# rev2.net
KiCad netlist of a schematic drawn in EAGLE
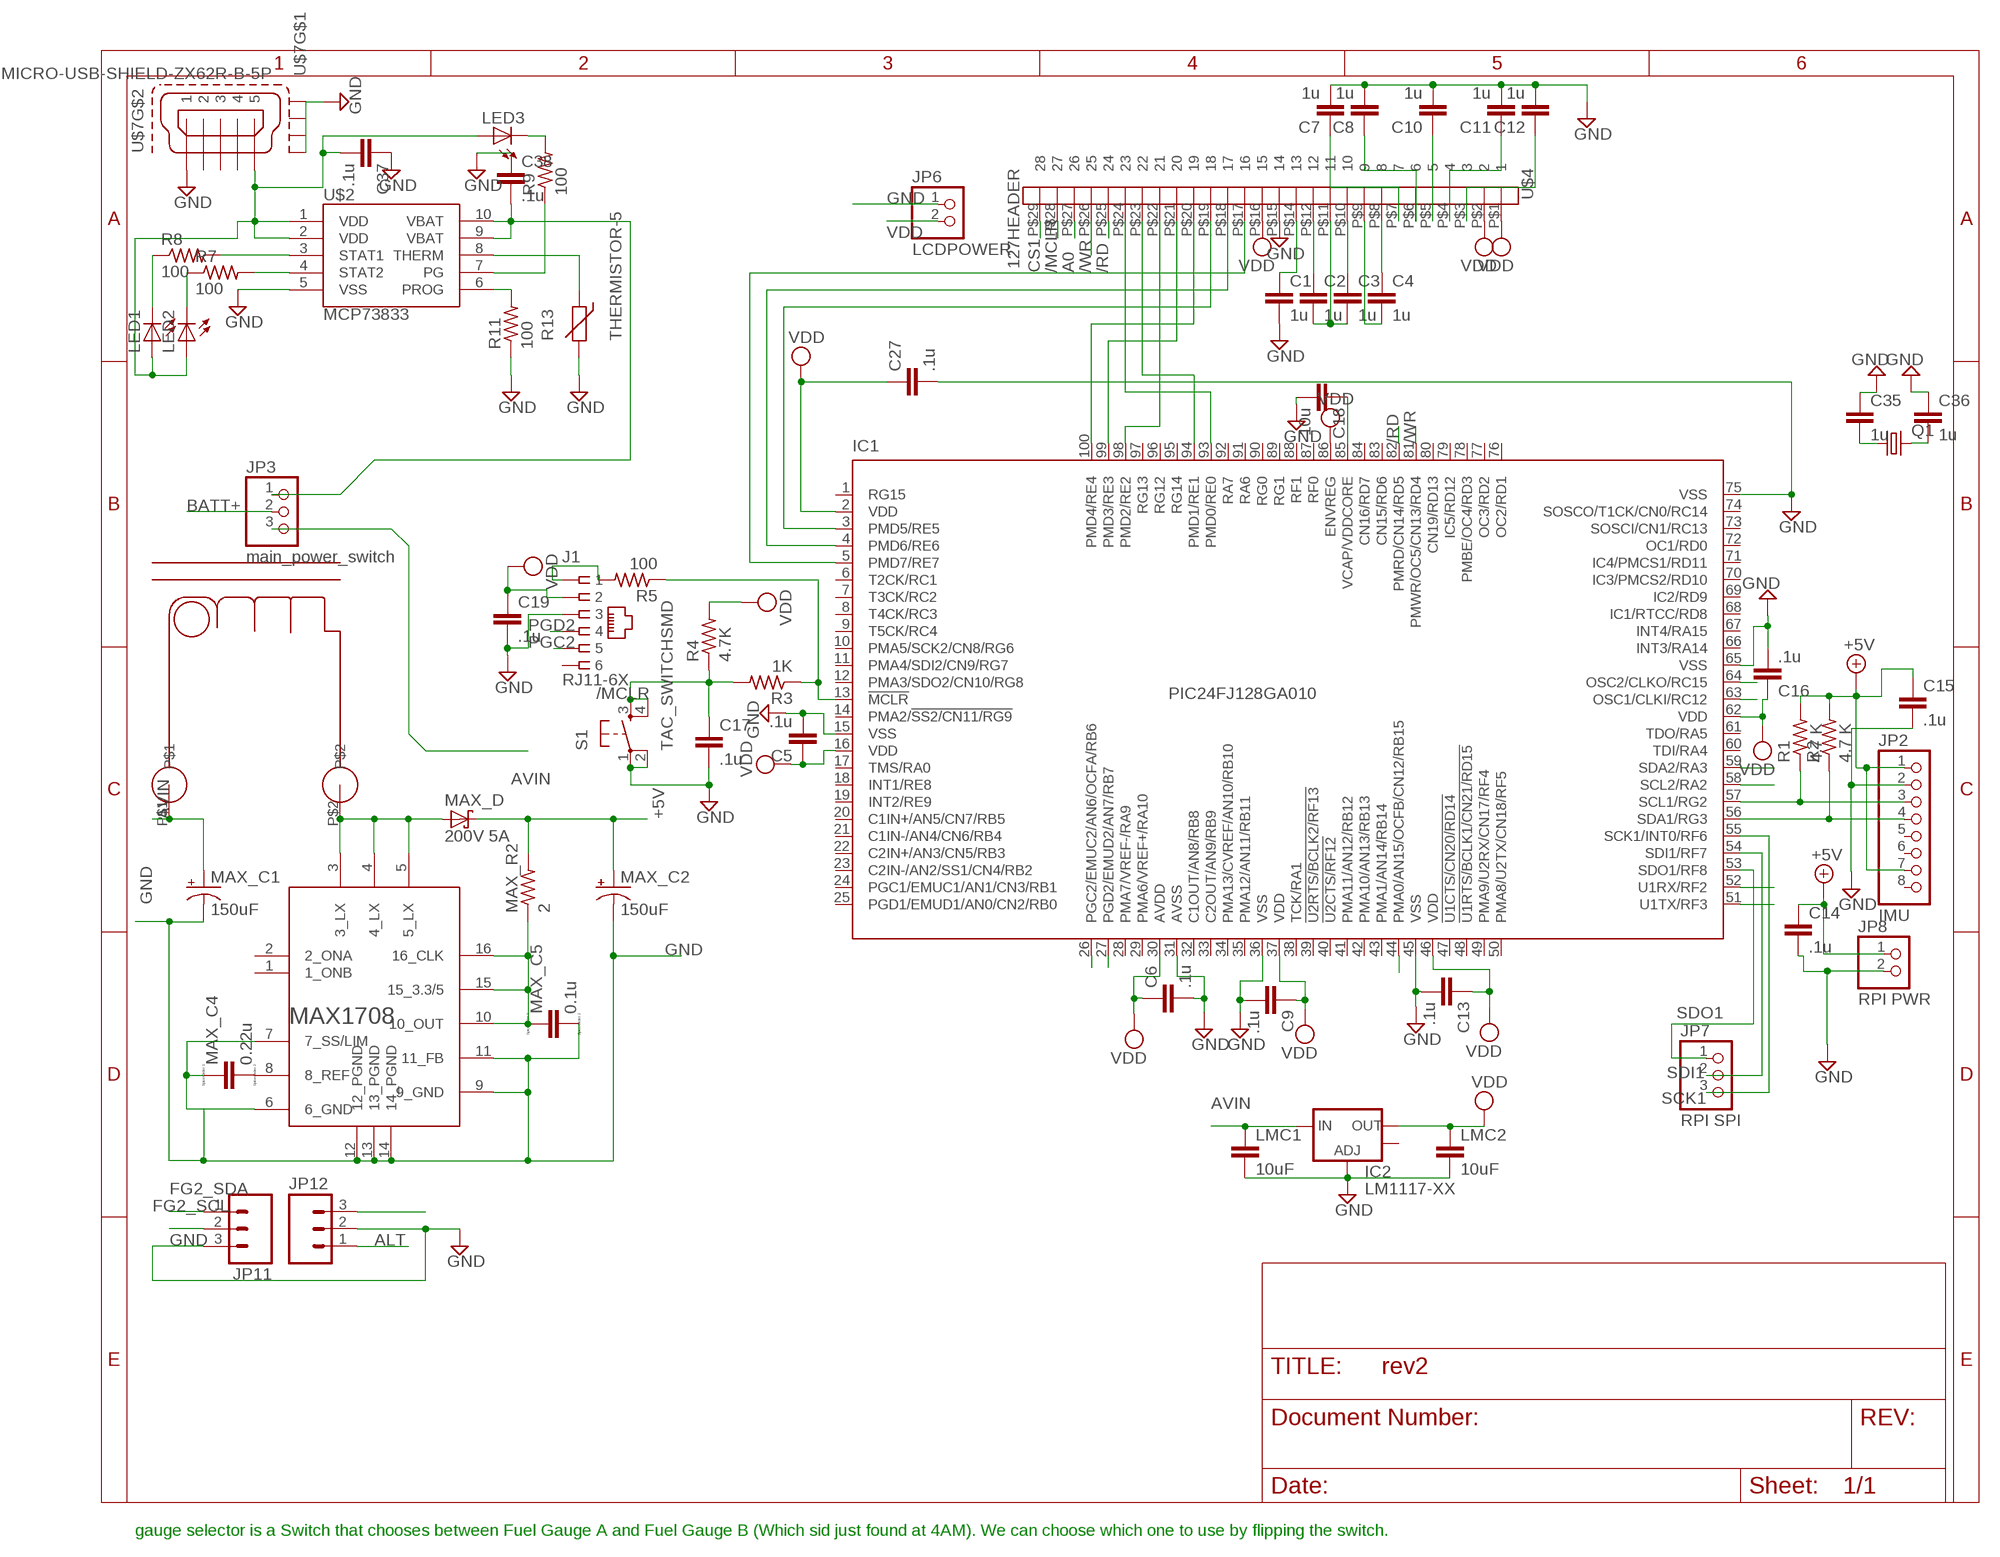
[diagram p0: schematic, sheet 1]

(export (version "E")
  (design (tool "Eeschema 10.0.6"))
  (components
    (comp (ref "C1")
      (value "1u")
      (footprint "eagle-import:C1206")
      (libsource (lib "eagle-import") (part "C-EUC1206"))
    )
    (comp (ref "C2")
      (value "1u")
      (footprint "eagle-import:C1206")
      (libsource (lib "eagle-import") (part "C-EUC1206"))
    )
    (comp (ref "C3")
      (value "1u")
      (footprint "eagle-import:C1206")
      (libsource (lib "eagle-import") (part "C-EUC1206"))
    )
    (comp (ref "C4")
      (value "1u")
      (footprint "eagle-import:C1206")
      (libsource (lib "eagle-import") (part "C-EUC1206"))
    )
    (comp (ref "C5")
      (value ".1u")
      (footprint "eagle-import:C1206")
      (libsource (lib "eagle-import") (part "C-EUC1206"))
    )
    (comp (ref "C6")
      (value ".1u")
      (footprint "eagle-import:C1206")
      (libsource (lib "eagle-import") (part "C-EUC1206"))
    )
    (comp (ref "C7")
      (value "1u")
      (footprint "eagle-import:C1206")
      (libsource (lib "eagle-import") (part "C-EUC1206"))
    )
    (comp (ref "C8")
      (value "1u")
      (footprint "eagle-import:C1206")
      (libsource (lib "eagle-import") (part "C-EUC1206"))
    )
    (comp (ref "C9")
      (value ".1u")
      (footprint "eagle-import:C1206")
      (libsource (lib "eagle-import") (part "C-EUC1206"))
    )
    (comp (ref "C10")
      (value "1u")
      (footprint "eagle-import:C1206")
      (libsource (lib "eagle-import") (part "C-EUC1206"))
    )
    (comp (ref "C11")
      (value "1u")
      (footprint "eagle-import:C1206")
      (libsource (lib "eagle-import") (part "C-EUC1206"))
    )
    (comp (ref "C12")
      (value "1u")
      (footprint "eagle-import:C1206")
      (libsource (lib "eagle-import") (part "C-EUC1206"))
    )
    (comp (ref "C13")
      (value ".1u")
      (footprint "eagle-import:C1206")
      (libsource (lib "eagle-import") (part "C-EUC1206"))
    )
    (comp (ref "C14")
      (value ".1u")
      (footprint "eagle-import:C1206")
      (libsource (lib "eagle-import") (part "C-EUC1206"))
    )
    (comp (ref "C15")
      (value ".1u")
      (footprint "eagle-import:C1206")
      (libsource (lib "eagle-import") (part "C-EUC1206"))
    )
    (comp (ref "C16")
      (value ".1u")
      (footprint "eagle-import:C1206")
      (libsource (lib "eagle-import") (part "C-EUC1206"))
    )
    (comp (ref "C17")
      (value ".1u")
      (footprint "eagle-import:C1206")
      (libsource (lib "eagle-import") (part "C-EUC1206"))
    )
    (comp (ref "C18")
      (value "10u")
      (footprint "eagle-import:C1206")
      (libsource (lib "eagle-import") (part "C-EUC1206"))
    )
    (comp (ref "C19")
      (value ".1u")
      (footprint "eagle-import:C1206")
      (libsource (lib "eagle-import") (part "C-EUC1206"))
    )
    (comp (ref "C27")
      (value ".1u")
      (footprint "eagle-import:C1206")
      (libsource (lib "eagle-import") (part "C-EUC1206"))
    )
    (comp (ref "C35")
      (value "1u")
      (footprint "eagle-import:C1206")
      (libsource (lib "eagle-import") (part "C-EUC1206"))
    )
    (comp (ref "C36")
      (value "1u")
      (footprint "eagle-import:C1206")
      (libsource (lib "eagle-import") (part "C-EUC1206"))
    )
    (comp (ref "C37")
      (value ".1u")
      (footprint "eagle-import:C1206")
      (libsource (lib "eagle-import") (part "C-EUC1206"))
    )
    (comp (ref "C38")
      (value ".1u")
      (footprint "eagle-import:C1206")
      (libsource (lib "eagle-import") (part "C-EUC1206"))
    )
    (comp (ref "IC1")
      (value "PIC24FJ128GA010")
      (footprint "eagle-import:TQFP100-14X14")
      (fields (field (name "MPN") "PIC24FJ128GA010-I/PT"))
      (libsource (lib "eagle-import") (part "PIC24FJGA010128"))
    )
    (comp (ref "IC2")
      (value "LM1117-XX")
      (footprint "eagle-import:SOT223")
      (libsource (lib "eagle-import") (part "V_REG_LM1117SOT223"))
    )
    (comp (ref "J1")
      (value "RJ11-6X")
      (footprint "eagle-import:RJ11-NO_SHIELD")
      (libsource (lib "eagle-import") (part "RJ11-6X"))
    )
    (comp (ref "JP2")
      (value "IMU")
      (footprint "eagle-import:1X08")
      (libsource (lib "eagle-import") (part "PINHD-1X8"))
    )
    (comp (ref "JP3")
      (value "main_power_switch")
      (footprint "eagle-import:1X03")
      (libsource (lib "eagle-import") (part "PINHD-1X3"))
    )
    (comp (ref "JP6")
      (value "LCDPOWER")
      (footprint "eagle-import:1X02")
      (libsource (lib "eagle-import") (part "PINHD-1X2"))
    )
    (comp (ref "JP7")
      (value "RPI SPI")
      (footprint "eagle-import:1X03")
      (libsource (lib "eagle-import") (part "PINHD-1X3"))
    )
    (comp (ref "JP8")
      (value "RPI PWR")
      (footprint "eagle-import:1X02")
      (libsource (lib "eagle-import") (part "PINHD-1X2"))
    )
    (comp (ref "JP11")
      (value "M03PTH")
      (footprint "eagle-import:1X03")
      (libsource (lib "eagle-import") (part "M03PTH"))
    )
    (comp (ref "JP12")
      (value "M03PTH")
      (footprint "eagle-import:1X03")
      (libsource (lib "eagle-import") (part "M03PTH"))
    )
    (comp (ref "LED1")
      (value "LEDSMT1206")
      (footprint "eagle-import:1206")
      (libsource (lib "eagle-import") (part "LEDSMT1206"))
    )
    (comp (ref "LED2")
      (value "LEDSMT1206")
      (footprint "eagle-import:1206")
      (libsource (lib "eagle-import") (part "LEDSMT1206"))
    )
    (comp (ref "LED3")
      (value "LEDSMT1206")
      (footprint "eagle-import:1206")
      (libsource (lib "eagle-import") (part "LEDSMT1206"))
    )
    (comp (ref "LMC1")
      (value "10uF")
      (footprint "eagle-import:C1206")
      (libsource (lib "eagle-import") (part "C-EUC1206"))
    )
    (comp (ref "LMC2")
      (value "10uF")
      (footprint "eagle-import:C1206")
      (libsource (lib "eagle-import") (part "C-EUC1206"))
    )
    (comp (ref "MAX_C1")
      (value "150uF")
      (footprint "eagle-import:CT7343")
      (libsource (lib "eagle-import") (part "CPOL-USCT7343"))
    )
    (comp (ref "MAX_C2")
      (value "150uF")
      (footprint "eagle-import:CT7343")
      (libsource (lib "eagle-import") (part "CPOL-USCT7343"))
    )
    (comp (ref "MAX_C4")
      (value "0.22u")
      (footprint "eagle-import:C1206")
      (libsource (lib "eagle-import") (part "CC1206"))
    )
    (comp (ref "MAX_C5")
      (value "0.1u")
      (footprint "eagle-import:C1206")
      (libsource (lib "eagle-import") (part "CC1206"))
    )
    (comp (ref "MAX_D")
      (value "200V 5A")
      (footprint "eagle-import:SMC")
      (libsource (lib "eagle-import") (part "SCHOTTKY-DIODESMC"))
    )
    (comp (ref "MAX_R2")
      (value "2")
      (footprint "eagle-import:R1206")
      (libsource (lib "eagle-import") (part "R-US_R1206"))
    )
    (comp (ref "Q1")
      (value "CRYTALHC49U-V")
      (footprint "eagle-import:HC49U-V")
      (libsource (lib "eagle-import") (part "CRYTALHC49U-V"))
    )
    (comp (ref "R1")
      (value "4.7 K")
      (footprint "eagle-import:R1206")
      (libsource (lib "eagle-import") (part "rcl_R-US_R1206"))
    )
    (comp (ref "R2")
      (value "4.7 K")
      (footprint "eagle-import:R1206")
      (libsource (lib "eagle-import") (part "rcl_R-US_R1206"))
    )
    (comp (ref "R3")
      (value "1K")
      (footprint "eagle-import:R1206")
      (libsource (lib "eagle-import") (part "rcl_R-US_R1206"))
    )
    (comp (ref "R4")
      (value "4.7K")
      (footprint "eagle-import:R1206")
      (libsource (lib "eagle-import") (part "rcl_R-US_R1206"))
    )
    (comp (ref "R5")
      (value "100")
      (footprint "eagle-import:R1206")
      (libsource (lib "eagle-import") (part "rcl_R-US_R1206"))
    )
    (comp (ref "R7")
      (value "100")
      (footprint "eagle-import:R1206")
      (libsource (lib "eagle-import") (part "rcl_R-US_R1206"))
    )
    (comp (ref "R8")
      (value "100")
      (footprint "eagle-import:R1206")
      (libsource (lib "eagle-import") (part "rcl_R-US_R1206"))
    )
    (comp (ref "R9")
      (value "100")
      (footprint "eagle-import:R1206")
      (libsource (lib "eagle-import") (part "rcl_R-US_R1206"))
    )
    (comp (ref "R11")
      (value "100")
      (footprint "eagle-import:R1206")
      (libsource (lib "eagle-import") (part "rcl_R-US_R1206"))
    )
    (comp (ref "R13")
      (value "THERMISTOR-5")
      (footprint "eagle-import:R-5")
      (libsource (lib "eagle-import") (part "THERMISTOR-5"))
    )
    (comp (ref "S1")
      (value "TAC_SWITCHSMD")
      (footprint "eagle-import:TACTILE-SWITCH-SMD")
      (libsource (lib "eagle-import") (part "TAC_SWITCHSMD"))
    )
    (comp (ref "U$2")
      (value "MCP73833")
      (footprint "eagle-import:MSOP10")
      (libsource (lib "eagle-import") (part "MCP73833"))
    )
    (comp (ref "U$3")
      (value "MAX1708")
      (footprint "eagle-import:QSOP16")
      (libsource (lib "eagle-import") (part "MAX1708"))
    )
    (comp (ref "U$4")
      (value "127HEADER")
      (footprint "eagle-import:1.27HEADER")
      (libsource (lib "eagle-import") (part "127HEADER"))
    )
    (comp (ref "U$6")
      (value "UP2B-2R2-R")
      (footprint "eagle-import:UP2B-2R2-R")
      (libsource (lib "eagle-import") (part "UP2B-2R2-R"))
    )
    (comp (ref "U$7")
      (value "MICRO-USB-SHIELD-ZX62R-B-5P")
      (footprint "eagle-import:ZX62R-B-5P")
      (libsource (lib "eagle-import") (part "MICRO-USB-SHIELD-ZX62R-B-5P"))
    )
  )
  (nets
    (net (code "1") (name "+5V") (class "Default")
      (node (ref "C14") (pin "1") (pinfunction "1_1") (pintype "passive"))
      (node (ref "C15") (pin "1") (pinfunction "1_1") (pintype "passive"))
      (node (ref "JP2") (pin "1") (pinfunction "1_1") (pintype "passive"))
      (node (ref "JP2") (pin "7") (pinfunction "7_7") (pintype "passive"))
      (node (ref "JP8") (pin "1") (pinfunction "1_1") (pintype "passive"))
      (node (ref "MAX_C2") (pin "+") (pinfunction "+_+") (pintype "passive"))
      (node (ref "MAX_D") (pin "C") (pinfunction "C_C") (pintype "passive"))
      (node (ref "MAX_R2") (pin "2") (pinfunction "2_2") (pintype "passive"))
      (node (ref "R1") (pin "2") (pinfunction "2_2") (pintype "passive"))
      (node (ref "R2") (pin "2") (pinfunction "2_2") (pintype "passive"))
    )
    (net (code "2") (name "/A0") (class "Default")
      (node (ref "IC1") (pin "44") (pinfunction "PMA0/AN15/OCFB/CN12/RB15_44") (pintype "bidirectional"))
      (node (ref "U$4") (pin "P$27") (pinfunction "26_P$27") (pintype "bidirectional"))
    )
    (net (code "3") (name "/ALT") (class "Default")
      (node (ref "JP12") (pin "1") (pinfunction "1_1") (pintype "passive"))
    )
    (net (code "4") (name "/AVIN") (class "Default")
      (node (ref "IC2") (pin "3") (pinfunction "IN_3") (pintype "input"))
      (node (ref "JP3") (pin "3") (pinfunction "3_3") (pintype "passive"))
      (node (ref "LMC1") (pin "1") (pinfunction "1_1") (pintype "passive"))
      (node (ref "MAX_C1") (pin "+") (pinfunction "+_+") (pintype "passive"))
      (node (ref "U$6") (pin "P$1") (pinfunction "P$1_P$1") (pintype "bidirectional"))
    )
    (net (code "5") (name "/BATT+") (class "Default")
      (node (ref "JP12") (pin "3") (pinfunction "3_3") (pintype "passive"))
      (node (ref "JP3") (pin "2") (pinfunction "2_2") (pintype "passive"))
    )
    (net (code "6") (name "/CS1") (class "Default")
      (node (ref "U$4") (pin "P$29") (pinfunction "28_P$29") (pintype "bidirectional"))
    )
    (net (code "7") (name "/FG2_SCL") (class "Default")
      (node (ref "IC1") (pin "58") (pinfunction "SCL2/RA2_58") (pintype "bidirectional"))
      (node (ref "JP11") (pin "2") (pinfunction "2_2") (pintype "passive"))
    )
    (net (code "8") (name "/FG2_SDA") (class "Default")
      (node (ref "IC1") (pin "59") (pinfunction "SDA2/RA3_59") (pintype "bidirectional"))
      (node (ref "JP11") (pin "1") (pinfunction "1_1") (pintype "passive"))
    )
    (net (code "9") (name "/OSC1") (class "Default")
      (node (ref "C36") (pin "2") (pinfunction "2_2") (pintype "passive"))
      (node (ref "IC1") (pin "63") (pinfunction "OSC1/CLKI/RC12_63") (pintype "bidirectional"))
      (node (ref "Q1") (pin "2") (pinfunction "2_2") (pintype "passive"))
    )
    (net (code "10") (name "/OSC2") (class "Default")
      (node (ref "C35") (pin "2") (pinfunction "2_2") (pintype "passive"))
      (node (ref "IC1") (pin "64") (pinfunction "OSC2/CLKO/RC15_64") (pintype "bidirectional"))
      (node (ref "Q1") (pin "1") (pinfunction "1_1") (pintype "passive"))
    )
    (net (code "11") (name "/PGC2") (class "Default")
      (node (ref "IC1") (pin "26") (pinfunction "PGC2/EMUC2/AN6/OCFA/RB6_26") (pintype "bidirectional"))
      (node (ref "J1") (pin "5") (pinfunction "5_5") (pintype "passive"))
    )
    (net (code "12") (name "/PGD2") (class "Default")
      (node (ref "IC1") (pin "27") (pinfunction "PGD2/EMUD2/AN7/RB7_27") (pintype "bidirectional"))
      (node (ref "J1") (pin "4") (pinfunction "4_4") (pintype "passive"))
    )
    (net (code "13") (name "/SCK1") (class "Default")
      (node (ref "IC1") (pin "55") (pinfunction "SCK1/INT0/RF6_55") (pintype "bidirectional"))
      (node (ref "JP7") (pin "3") (pinfunction "3_3") (pintype "passive"))
    )
    (net (code "14") (name "/SDI1") (class "Default")
      (node (ref "IC1") (pin "54") (pinfunction "SDI1/RF7_54") (pintype "bidirectional"))
      (node (ref "JP7") (pin "2") (pinfunction "2_2") (pintype "passive"))
    )
    (net (code "15") (name "/SDO1") (class "Default")
      (node (ref "IC1") (pin "53") (pinfunction "SDO1/RF8_53") (pintype "bidirectional"))
      (node (ref "JP7") (pin "1") (pinfunction "1_1") (pintype "passive"))
    )
    (net (code "16") (name "/{slash}MCLR") (class "Default")
      (node (ref "C17") (pin "1") (pinfunction "1_1") (pintype "passive"))
      (node (ref "R3") (pin "2") (pinfunction "2_2") (pintype "passive"))
      (node (ref "R4") (pin "1") (pinfunction "1_1") (pintype "passive"))
      (node (ref "S1") (pin "3") (pinfunction "3_3") (pintype "passive"))
      (node (ref "S1") (pin "4") (pinfunction "4_4") (pintype "passive"))
      (node (ref "U$4") (pin "P$28") (pinfunction "27_P$28") (pintype "bidirectional"))
    )
    (net (code "17") (name "/{slash}RD") (class "Default")
      (node (ref "IC1") (pin "82") (pinfunction "PMRD/CN14/RD5_82") (pintype "bidirectional"))
      (node (ref "U$4") (pin "P$25") (pinfunction "24_P$25") (pintype "bidirectional"))
    )
    (net (code "18") (name "/{slash}WR") (class "Default")
      (node (ref "IC1") (pin "81") (pinfunction "PMWR/OC5/CN13/RD4_81") (pintype "bidirectional"))
      (node (ref "U$4") (pin "P$26") (pinfunction "25_P$26") (pintype "bidirectional"))
    )
    (net (code "19") (name "GND") (class "Default")
      (node (ref "C1") (pin "2") (pinfunction "2_2") (pintype "passive"))
      (node (ref "C10") (pin "2") (pinfunction "2_2") (pintype "passive"))
      (node (ref "C11") (pin "2") (pinfunction "2_2") (pintype "passive"))
      (node (ref "C12") (pin "2") (pinfunction "2_2") (pintype "passive"))
      (node (ref "C13") (pin "2") (pinfunction "2_2") (pintype "passive"))
      (node (ref "C14") (pin "2") (pinfunction "2_2") (pintype "passive"))
      (node (ref "C15") (pin "2") (pinfunction "2_2") (pintype "passive"))
      (node (ref "C16") (pin "2") (pinfunction "2_2") (pintype "passive"))
      (node (ref "C17") (pin "2") (pinfunction "2_2") (pintype "passive"))
      (node (ref "C18") (pin "2") (pinfunction "2_2") (pintype "passive"))
      (node (ref "C19") (pin "2") (pinfunction "2_2") (pintype "passive"))
      (node (ref "C27") (pin "2") (pinfunction "2_2") (pintype "passive"))
      (node (ref "C35") (pin "1") (pinfunction "1_1") (pintype "passive"))
      (node (ref "C36") (pin "1") (pinfunction "1_1") (pintype "passive"))
      (node (ref "C37") (pin "1") (pinfunction "1_1") (pintype "passive"))
      (node (ref "C38") (pin "1") (pinfunction "1_1") (pintype "passive"))
      (node (ref "C5") (pin "2") (pinfunction "2_2") (pintype "passive"))
      (node (ref "C6") (pin "2") (pinfunction "2_2") (pintype "passive"))
      (node (ref "C7") (pin "2") (pinfunction "2_2") (pintype "passive"))
      (node (ref "C8") (pin "2") (pinfunction "2_2") (pintype "passive"))
      (node (ref "C9") (pin "2") (pinfunction "2_2") (pintype "passive"))
      (node (ref "IC1") (pin "15") (pinfunction "VSS_15") (pintype "power_in"))
      (node (ref "IC1") (pin "31") (pinfunction "AVSS_31") (pintype "power_in"))
      (node (ref "IC1") (pin "36") (pinfunction "VSS_36") (pintype "power_in"))
      (node (ref "IC1") (pin "45") (pinfunction "VSS_45") (pintype "power_in"))
      (node (ref "IC1") (pin "65") (pinfunction "VSS_65") (pintype "power_in"))
      (node (ref "IC1") (pin "75") (pinfunction "VSS_75") (pintype "power_in"))
      (node (ref "IC2") (pin "1") (pinfunction "ADJ_1") (pintype "input"))
      (node (ref "J1") (pin "3") (pinfunction "3_3") (pintype "passive"))
      (node (ref "JP11") (pin "3") (pinfunction "3_3") (pintype "passive"))
      (node (ref "JP12") (pin "2") (pinfunction "2_2") (pintype "passive"))
      (node (ref "JP2") (pin "2") (pinfunction "2_2") (pintype "passive"))
      (node (ref "JP6") (pin "1") (pinfunction "1_1") (pintype "passive"))
      (node (ref "JP8") (pin "2") (pinfunction "2_2") (pintype "passive"))
      (node (ref "LMC1") (pin "2") (pinfunction "2_2") (pintype "passive"))
      (node (ref "LMC2") (pin "2") (pinfunction "2_2") (pintype "passive"))
      (node (ref "MAX_C1") (pin "-") (pinfunction "-_-") (pintype "passive"))
      (node (ref "MAX_C2") (pin "-") (pinfunction "-_-") (pintype "passive"))
      (node (ref "MAX_C4") (pin "1") (pinfunction "1_1") (pintype "passive"))
      (node (ref "MAX_C5") (pin "2") (pinfunction "2_2") (pintype "passive"))
      (node (ref "R11") (pin "1") (pinfunction "1_1") (pintype "passive"))
      (node (ref "R13") (pin "2") (pinfunction "2_2") (pintype "passive"))
      (node (ref "S1") (pin "1") (pinfunction "1_1") (pintype "passive"))
      (node (ref "S1") (pin "2") (pinfunction "2_2") (pintype "passive"))
      (node (ref "U$2") (pin "5") (pinfunction "VSS_5") (pintype "bidirectional"))
      (node (ref "U$3") (pin "11") (pinfunction "11_FB_11") (pintype "bidirectional"))
      (node (ref "U$3") (pin "12") (pinfunction "12_PGND_12") (pintype "bidirectional"))
      (node (ref "U$3") (pin "13") (pinfunction "13_PGND_13") (pintype "bidirectional"))
      (node (ref "U$3") (pin "14") (pinfunction "14_PGND_14") (pintype "bidirectional"))
      (node (ref "U$3") (pin "6") (pinfunction "6_GND_6") (pintype "bidirectional"))
      (node (ref "U$3") (pin "7") (pinfunction "7_SS/LIM_7") (pintype "bidirectional"))
      (node (ref "U$3") (pin "9") (pinfunction "9_GND_9") (pintype "bidirectional"))
      (node (ref "U$4") (pin "P$15") (pinfunction "14_P$15") (pintype "bidirectional"))
      (node (ref "U$7") (pin "1") (pinfunction "1_1") (pintype "input"))
      (node (ref "U$7") (pin "M1") (pinfunction "S1_M1") (pintype "passive"))
      (node (ref "U$7") (pin "M2") (pinfunction "S2_M2") (pintype "passive"))
      (node (ref "U$7") (pin "M3") (pinfunction "S3_M3") (pintype "passive"))
      (node (ref "U$7") (pin "M4") (pinfunction "S4_M4") (pintype "passive"))
    )
    (net (code "20") (name "Net-(C37-Pad2)") (class "Default")
      (node (ref "C37") (pin "2") (pinfunction "2_2") (pintype "passive"))
      (node (ref "LED1") (pin "A") (pinfunction "A_A") (pintype "passive"))
      (node (ref "LED2") (pin "A") (pinfunction "A_A") (pintype "passive"))
      (node (ref "LED3") (pin "A") (pinfunction "A_A") (pintype "passive"))
      (node (ref "U$2") (pin "1") (pinfunction "VDD_1") (pintype "bidirectional"))
      (node (ref "U$2") (pin "2") (pinfunction "VDD_2") (pintype "bidirectional"))
      (node (ref "U$7") (pin "5") (pinfunction "5_5") (pintype "input"))
    )
    (net (code "21") (name "Net-(C38-Pad2)") (class "Default")
      (node (ref "C38") (pin "2") (pinfunction "2_2") (pintype "passive"))
      (node (ref "JP3") (pin "1") (pinfunction "1_1") (pintype "passive"))
      (node (ref "U$2") (pin "10") (pinfunction "VBAT_10") (pintype "bidirectional"))
      (node (ref "U$2") (pin "9") (pinfunction "VBAT_9") (pintype "bidirectional"))
    )
    (net (code "22") (name "Net-(IC1-PMD0{slash}RE0)") (class "Default")
      (node (ref "IC1") (pin "93") (pinfunction "PMD0/RE0_93") (pintype "bidirectional"))
      (node (ref "U$4") (pin "P$24") (pinfunction "23_P$24") (pintype "bidirectional"))
    )
    (net (code "23") (name "Net-(IC1-PMD1{slash}RE1)") (class "Default")
      (node (ref "IC1") (pin "94") (pinfunction "PMD1/RE1_94") (pintype "bidirectional"))
      (node (ref "U$4") (pin "P$23") (pinfunction "22_P$23") (pintype "bidirectional"))
    )
    (net (code "24") (name "Net-(IC1-PMD2{slash}RE2)") (class "Default")
      (node (ref "IC1") (pin "98") (pinfunction "PMD2/RE2_98") (pintype "bidirectional"))
      (node (ref "U$4") (pin "P$22") (pinfunction "21_P$22") (pintype "bidirectional"))
    )
    (net (code "25") (name "Net-(IC1-PMD3{slash}RE3)") (class "Default")
      (node (ref "IC1") (pin "99") (pinfunction "PMD3/RE3_99") (pintype "bidirectional"))
      (node (ref "U$4") (pin "P$21") (pinfunction "20_P$21") (pintype "bidirectional"))
    )
    (net (code "26") (name "Net-(IC1-PMD4{slash}RE4)") (class "Default")
      (node (ref "IC1") (pin "100") (pinfunction "PMD4/RE4_100") (pintype "bidirectional"))
      (node (ref "U$4") (pin "P$20") (pinfunction "19_P$20") (pintype "bidirectional"))
    )
    (net (code "27") (name "Net-(IC1-PMD5{slash}RE5)") (class "Default")
      (node (ref "IC1") (pin "3") (pinfunction "PMD5/RE5_3") (pintype "bidirectional"))
      (node (ref "U$4") (pin "P$19") (pinfunction "18_P$19") (pintype "bidirectional"))
    )
    (net (code "28") (name "Net-(IC1-PMD6{slash}RE6)") (class "Default")
      (node (ref "IC1") (pin "4") (pinfunction "PMD6/RE6_4") (pintype "bidirectional"))
      (node (ref "U$4") (pin "P$18") (pinfunction "17_P$18") (pintype "bidirectional"))
    )
    (net (code "29") (name "Net-(IC1-PMD7{slash}RE7)") (class "Default")
      (node (ref "IC1") (pin "5") (pinfunction "PMD7/RE7_5") (pintype "bidirectional"))
      (node (ref "U$4") (pin "P$17") (pinfunction "16_P$17") (pintype "bidirectional"))
    )
    (net (code "30") (name "Net-(IC1-SCL1{slash}RG2)") (class "Default")
      (node (ref "IC1") (pin "57") (pinfunction "SCL1/RG2_57") (pintype "bidirectional"))
      (node (ref "JP2") (pin "3") (pinfunction "3_3") (pintype "passive"))
      (node (ref "R1") (pin "1") (pinfunction "1_1") (pintype "passive"))
    )
    (net (code "31") (name "Net-(IC1-SDA1{slash}RG3)") (class "Default")
      (node (ref "IC1") (pin "56") (pinfunction "SDA1/RG3_56") (pintype "bidirectional"))
      (node (ref "JP2") (pin "4") (pinfunction "4_4") (pintype "passive"))
      (node (ref "R2") (pin "1") (pinfunction "1_1") (pintype "passive"))
    )
    (net (code "32") (name "Net-(IC1-VCAP{slash}VDDCORE)") (class "Default")
      (node (ref "C18") (pin "1") (pinfunction "1_1") (pintype "passive"))
      (node (ref "IC1") (pin "85") (pinfunction "VCAP/VDDCORE_85") (pintype "bidirectional"))
    )
    (net (code "33") (name "Net-(IC1-~{MCLR})") (class "Default")
      (node (ref "IC1") (pin "13") (pinfunction "~{MCLR}_13") (pintype "bidirectional"))
      (node (ref "R3") (pin "1") (pinfunction "1_1") (pintype "passive"))
      (node (ref "R5") (pin "1") (pinfunction "1_1") (pintype "passive"))
    )
    (net (code "34") (name "Net-(J1-Pad1)") (class "Default")
      (node (ref "J1") (pin "1") (pinfunction "1_1") (pintype "passive"))
      (node (ref "R5") (pin "2") (pinfunction "2_2") (pintype "passive"))
    )
    (net (code "35") (name "Net-(LED1-PadC)") (class "Default")
      (node (ref "LED1") (pin "C") (pinfunction "C_C") (pintype "passive"))
      (node (ref "R8") (pin "1") (pinfunction "1_1") (pintype "passive"))
    )
    (net (code "36") (name "Net-(LED2-PadC)") (class "Default")
      (node (ref "LED2") (pin "C") (pinfunction "C_C") (pintype "passive"))
      (node (ref "R7") (pin "1") (pinfunction "1_1") (pintype "passive"))
    )
    (net (code "37") (name "Net-(LED3-PadC)") (class "Default")
      (node (ref "LED3") (pin "C") (pinfunction "C_C") (pintype "passive"))
      (node (ref "R9") (pin "2") (pinfunction "2_2") (pintype "passive"))
    )
    (net (code "38") (name "Net-(U$2-PG)") (class "Default")
      (node (ref "R9") (pin "1") (pinfunction "1_1") (pintype "passive"))
      (node (ref "U$2") (pin "7") (pinfunction "PG_7") (pintype "bidirectional"))
    )
    (net (code "39") (name "Net-(U$2-PROG)") (class "Default")
      (node (ref "R11") (pin "2") (pinfunction "2_2") (pintype "passive"))
      (node (ref "U$2") (pin "6") (pinfunction "PROG_6") (pintype "bidirectional"))
    )
    (net (code "40") (name "Net-(U$2-STAT1)") (class "Default")
      (node (ref "R8") (pin "2") (pinfunction "2_2") (pintype "passive"))
      (node (ref "U$2") (pin "3") (pinfunction "STAT1_3") (pintype "bidirectional"))
    )
    (net (code "41") (name "Net-(U$2-STAT2)") (class "Default")
      (node (ref "R7") (pin "2") (pinfunction "2_2") (pintype "passive"))
      (node (ref "U$2") (pin "4") (pinfunction "STAT2_4") (pintype "bidirectional"))
    )
    (net (code "42") (name "Net-(U$2-THERM)") (class "Default")
      (node (ref "R13") (pin "1") (pinfunction "1_1") (pintype "passive"))
      (node (ref "U$2") (pin "8") (pinfunction "THERM_8") (pintype "bidirectional"))
    )
    (net (code "43") (name "Net-(U$3-3_LX)") (class "Default")
      (node (ref "MAX_D") (pin "A") (pinfunction "A_A") (pintype "passive"))
      (node (ref "U$3") (pin "3") (pinfunction "3_LX_3") (pintype "bidirectional"))
      (node (ref "U$3") (pin "4") (pinfunction "4_LX_4") (pintype "bidirectional"))
      (node (ref "U$3") (pin "5") (pinfunction "5_LX_5") (pintype "bidirectional"))
      (node (ref "U$6") (pin "P$2") (pinfunction "P$2_P$2") (pintype "bidirectional"))
    )
    (net (code "44") (name "Net-(U$3-8_REF)") (class "Default")
      (node (ref "MAX_C4") (pin "2") (pinfunction "2_2") (pintype "passive"))
      (node (ref "U$3") (pin "8") (pinfunction "8_REF_8") (pintype "bidirectional"))
    )
    (net (code "45") (name "Net-(U$3-10_OUT)") (class "Default")
      (node (ref "MAX_C5") (pin "1") (pinfunction "1_1") (pintype "passive"))
      (node (ref "MAX_R2") (pin "1") (pinfunction "1_1") (pintype "passive"))
      (node (ref "U$3") (pin "10") (pinfunction "10_OUT_10") (pintype "bidirectional"))
      (node (ref "U$3") (pin "15") (pinfunction "15_3.3/5_15") (pintype "bidirectional"))
      (node (ref "U$3") (pin "16") (pinfunction "16_CLK_16") (pintype "bidirectional"))
    )
    (net (code "46") (name "Net-(U$4-3)") (class "Default")
      (node (ref "C12") (pin "1") (pinfunction "1_1") (pintype "passive"))
      (node (ref "U$4") (pin "P$3") (pinfunction "3_P$3") (pintype "bidirectional"))
    )
    (net (code "47") (name "Net-(U$4-4)") (class "Default")
      (node (ref "C11") (pin "1") (pinfunction "1_1") (pintype "passive"))
      (node (ref "U$4") (pin "P$4") (pinfunction "4_P$4") (pintype "bidirectional"))
    )
    (net (code "48") (name "Net-(U$4-5)") (class "Default")
      (node (ref "C10") (pin "1") (pinfunction "1_1") (pintype "passive"))
      (node (ref "U$4") (pin "P$5") (pinfunction "5_P$5") (pintype "bidirectional"))
    )
    (net (code "49") (name "Net-(U$4-6)") (class "Default")
      (node (ref "C8") (pin "1") (pinfunction "1_1") (pintype "passive"))
      (node (ref "U$4") (pin "P$6") (pinfunction "6_P$6") (pintype "bidirectional"))
    )
    (net (code "50") (name "Net-(U$4-7)") (class "Default")
      (node (ref "C7") (pin "1") (pinfunction "1_1") (pintype "passive"))
      (node (ref "U$4") (pin "P$7") (pinfunction "7_P$7") (pintype "bidirectional"))
    )
    (net (code "51") (name "Net-(U$4-8)") (class "Default")
      (node (ref "C4") (pin "1") (pinfunction "1_1") (pintype "passive"))
      (node (ref "U$4") (pin "P$8") (pinfunction "8_P$8") (pintype "bidirectional"))
    )
    (net (code "52") (name "Net-(U$4-9)") (class "Default")
      (node (ref "C4") (pin "2") (pinfunction "2_2") (pintype "passive"))
      (node (ref "U$4") (pin "P$9") (pinfunction "9_P$9") (pintype "bidirectional"))
    )
    (net (code "53") (name "Net-(U$4-10)") (class "Default")
      (node (ref "C3") (pin "1") (pinfunction "1_1") (pintype "passive"))
      (node (ref "U$4") (pin "P$10") (pinfunction "10_P$10") (pintype "bidirectional"))
    )
    (net (code "54") (name "Net-(U$4-11)") (class "Default")
      (node (ref "C2") (pin "2") (pinfunction "2_2") (pintype "passive"))
      (node (ref "C3") (pin "2") (pinfunction "2_2") (pintype "passive"))
      (node (ref "U$4") (pin "P$11") (pinfunction "11_P$11") (pintype "bidirectional"))
    )
    (net (code "55") (name "Net-(U$4-12)") (class "Default")
      (node (ref "C2") (pin "1") (pinfunction "1_1") (pintype "passive"))
      (node (ref "U$4") (pin "P$12") (pinfunction "12_P$12") (pintype "bidirectional"))
    )
    (net (code "56") (name "Net-(U$4-13)") (class "Default")
      (node (ref "C1") (pin "1") (pinfunction "1_1") (pintype "passive"))
      (node (ref "U$4") (pin "P$14") (pinfunction "13_P$14") (pintype "bidirectional"))
    )
    (net (code "57") (name "VDD") (class "Default")
      (node (ref "C13") (pin "1") (pinfunction "1_1") (pintype "passive"))
      (node (ref "C16") (pin "1") (pinfunction "1_1") (pintype "passive"))
      (node (ref "C19") (pin "1") (pinfunction "1_1") (pintype "passive"))
      (node (ref "C27") (pin "1") (pinfunction "1_1") (pintype "passive"))
      (node (ref "C5") (pin "1") (pinfunction "1_1") (pintype "passive"))
      (node (ref "C6") (pin "1") (pinfunction "1_1") (pintype "passive"))
      (node (ref "C9") (pin "1") (pinfunction "1_1") (pintype "passive"))
      (node (ref "IC1") (pin "16") (pinfunction "VDD_16") (pintype "power_in"))
      (node (ref "IC1") (pin "2") (pinfunction "VDD_2") (pintype "power_in"))
      (node (ref "IC1") (pin "30") (pinfunction "AVDD_30") (pintype "power_in"))
      (node (ref "IC1") (pin "37") (pinfunction "VDD_37") (pintype "power_in"))
      (node (ref "IC1") (pin "46") (pinfunction "VDD_46") (pintype "power_in"))
      (node (ref "IC1") (pin "62") (pinfunction "VDD_62") (pintype "power_in"))
      (node (ref "IC1") (pin "86") (pinfunction "ENVREG_86") (pintype "bidirectional"))
      (node (ref "IC2") (pin "2") (pinfunction "OUT_2") (pintype "output"))
      (node (ref "J1") (pin "2") (pinfunction "2_2") (pintype "passive"))
      (node (ref "JP6") (pin "2") (pinfunction "2_2") (pintype "passive"))
      (node (ref "LMC2") (pin "1") (pinfunction "1_1") (pintype "passive"))
      (node (ref "R4") (pin "2") (pinfunction "2_2") (pintype "passive"))
      (node (ref "U$4") (pin "P$1") (pinfunction "1_P$1") (pintype "bidirectional"))
      (node (ref "U$4") (pin "P$16") (pinfunction "15_P$16") (pintype "bidirectional"))
      (node (ref "U$4") (pin "P$2") (pinfunction "2_P$2") (pintype "bidirectional"))
    )
    (net (code "58") (name "unconnected-(IC1-C1IN+{slash}AN5{slash}CN7{slash}RB5-Pad20)") (class "Default")
      (node (ref "IC1") (pin "20") (pinfunction "C1IN+/AN5/CN7/RB5_20") (pintype "bidirectional"))
    )
    (net (code "59") (name "unconnected-(IC1-C1IN-{slash}AN4{slash}CN6{slash}RB4-Pad21)") (class "Default")
      (node (ref "IC1") (pin "21") (pinfunction "C1IN-/AN4/CN6/RB4_21") (pintype "bidirectional"))
    )
    (net (code "60") (name "unconnected-(IC1-C1OUT{slash}AN8{slash}RB8-Pad32)") (class "Default")
      (node (ref "IC1") (pin "32") (pinfunction "C1OUT/AN8/RB8_32") (pintype "bidirectional"))
    )
    (net (code "61") (name "unconnected-(IC1-C2IN+{slash}AN3{slash}CN5{slash}RB3-Pad22)") (class "Default")
      (node (ref "IC1") (pin "22") (pinfunction "C2IN+/AN3/CN5/RB3_22") (pintype "bidirectional"))
    )
    (net (code "62") (name "unconnected-(IC1-C2IN-{slash}AN2{slash}SS1{slash}CN4{slash}RB2-Pad23)") (class "Default")
      (node (ref "IC1") (pin "23") (pinfunction "C2IN-/AN2/SS1/CN4/RB2_23") (pintype "bidirectional"))
    )
    (net (code "63") (name "unconnected-(IC1-C2OUT{slash}AN9{slash}RB9-Pad33)") (class "Default")
      (node (ref "IC1") (pin "33") (pinfunction "C2OUT/AN9/RB9_33") (pintype "bidirectional"))
    )
    (net (code "64") (name "unconnected-(IC1-CN15{slash}RD6-Pad83)") (class "Default")
      (node (ref "IC1") (pin "83") (pinfunction "CN15/RD6_83") (pintype "bidirectional"))
    )
    (net (code "65") (name "unconnected-(IC1-CN16{slash}RD7-Pad84)") (class "Default")
      (node (ref "IC1") (pin "84") (pinfunction "CN16/RD7_84") (pintype "bidirectional"))
    )
    (net (code "66") (name "unconnected-(IC1-CN19{slash}RD13-Pad80)") (class "Default")
      (node (ref "IC1") (pin "80") (pinfunction "CN19/RD13_80") (pintype "bidirectional"))
    )
    (net (code "67") (name "unconnected-(IC1-IC1{slash}RTCC{slash}RD8-Pad68)") (class "Default")
      (node (ref "IC1") (pin "68") (pinfunction "IC1/RTCC/RD8_68") (pintype "bidirectional"))
    )
    (net (code "68") (name "unconnected-(IC1-IC2{slash}RD9-Pad69)") (class "Default")
      (node (ref "IC1") (pin "69") (pinfunction "IC2/RD9_69") (pintype "bidirectional"))
    )
    (net (code "69") (name "unconnected-(IC1-IC3{slash}PMCS2{slash}RD10-Pad70)") (class "Default")
      (node (ref "IC1") (pin "70") (pinfunction "IC3/PMCS2/RD10_70") (pintype "bidirectional"))
    )
    (net (code "70") (name "unconnected-(IC1-IC4{slash}PMCS1{slash}RD11-Pad71)") (class "Default")
      (node (ref "IC1") (pin "71") (pinfunction "IC4/PMCS1/RD11_71") (pintype "bidirectional"))
    )
    (net (code "71") (name "unconnected-(IC1-IC5{slash}RD12-Pad79)") (class "Default")
      (node (ref "IC1") (pin "79") (pinfunction "IC5/RD12_79") (pintype "bidirectional"))
    )
    (net (code "72") (name "unconnected-(IC1-INT1{slash}RE8-Pad18)") (class "Default")
      (node (ref "IC1") (pin "18") (pinfunction "INT1/RE8_18") (pintype "bidirectional"))
    )
    (net (code "73") (name "unconnected-(IC1-INT2{slash}RE9-Pad19)") (class "Default")
      (node (ref "IC1") (pin "19") (pinfunction "INT2/RE9_19") (pintype "bidirectional"))
    )
    (net (code "74") (name "unconnected-(IC1-INT3{slash}RA14-Pad66)") (class "Default")
      (node (ref "IC1") (pin "66") (pinfunction "INT3/RA14_66") (pintype "bidirectional"))
    )
    (net (code "75") (name "unconnected-(IC1-INT4{slash}RA15-Pad67)") (class "Default")
      (node (ref "IC1") (pin "67") (pinfunction "INT4/RA15_67") (pintype "bidirectional"))
    )
    (net (code "76") (name "unconnected-(IC1-OC1{slash}RD0-Pad72)") (class "Default")
      (node (ref "IC1") (pin "72") (pinfunction "OC1/RD0_72") (pintype "bidirectional"))
    )
    (net (code "77") (name "unconnected-(IC1-OC2{slash}RD1-Pad76)") (class "Default")
      (node (ref "IC1") (pin "76") (pinfunction "OC2/RD1_76") (pintype "bidirectional"))
    )
    (net (code "78") (name "unconnected-(IC1-OC3{slash}RD2-Pad77)") (class "Default")
      (node (ref "IC1") (pin "77") (pinfunction "OC3/RD2_77") (pintype "bidirectional"))
    )
    (net (code "79") (name "unconnected-(IC1-PGC1{slash}EMUC1{slash}AN1{slash}CN3{slash}RB1-Pad24)") (class "Default")
      (node (ref "IC1") (pin "24") (pinfunction "PGC1/EMUC1/AN1/CN3/RB1_24") (pintype "bidirectional"))
    )
    (net (code "80") (name "unconnected-(IC1-PGD1{slash}EMUD1{slash}AN0{slash}CN2{slash}RB0-Pad25)") (class "Default")
      (node (ref "IC1") (pin "25") (pinfunction "PGD1/EMUD1/AN0/CN2/RB0_25") (pintype "bidirectional"))
    )
    (net (code "81") (name "unconnected-(IC1-PMA1{slash}AN14{slash}RB14-Pad43)") (class "Default")
      (node (ref "IC1") (pin "43") (pinfunction "PMA1/AN14/RB14_43") (pintype "bidirectional"))
    )
    (net (code "82") (name "unconnected-(IC1-PMA2{slash}~{SS2{slash}CN11{slash}RG9}-Pad14)") (class "Default")
      (node (ref "IC1") (pin "14") (pinfunction "PMA2/~{SS2/CN11/RG9}_14") (pintype "bidirectional"))
    )
    (net (code "83") (name "unconnected-(IC1-PMA3{slash}SDO2{slash}CN10{slash}RG8-Pad12)") (class "Default")
      (node (ref "IC1") (pin "12") (pinfunction "PMA3/SDO2/CN10/RG8_12") (pintype "bidirectional"))
    )
    (net (code "84") (name "unconnected-(IC1-PMA4{slash}SDI2{slash}CN9{slash}RG7-Pad11)") (class "Default")
      (node (ref "IC1") (pin "11") (pinfunction "PMA4/SDI2/CN9/RG7_11") (pintype "bidirectional"))
    )
    (net (code "85") (name "unconnected-(IC1-PMA5{slash}SCK2{slash}CN8{slash}RG6-Pad10)") (class "Default")
      (node (ref "IC1") (pin "10") (pinfunction "PMA5/SCK2/CN8/RG6_10") (pintype "bidirectional"))
    )
    (net (code "86") (name "unconnected-(IC1-PMA6{slash}VREF+{slash}RA10-Pad29)") (class "Default")
      (node (ref "IC1") (pin "29") (pinfunction "PMA6/VREF+/RA10_29") (pintype "bidirectional"))
    )
    (net (code "87") (name "unconnected-(IC1-PMA7{slash}VREF-{slash}RA9-Pad28)") (class "Default")
      (node (ref "IC1") (pin "28") (pinfunction "PMA7/VREF-/RA9_28") (pintype "bidirectional"))
    )
    (net (code "88") (name "unconnected-(IC1-PMA8{slash}U2TX{slash}CN18{slash}RF5-Pad50)") (class "Default")
      (node (ref "IC1") (pin "50") (pinfunction "PMA8/U2TX/CN18/RF5_50") (pintype "bidirectional"))
    )
    (net (code "89") (name "unconnected-(IC1-PMA9{slash}U2RX{slash}CN17{slash}RF4-Pad49)") (class "Default")
      (node (ref "IC1") (pin "49") (pinfunction "PMA9/U2RX/CN17/RF4_49") (pintype "bidirectional"))
    )
    (net (code "90") (name "unconnected-(IC1-PMA10{slash}AN13{slash}RB13-Pad42)") (class "Default")
      (node (ref "IC1") (pin "42") (pinfunction "PMA10/AN13/RB13_42") (pintype "bidirectional"))
    )
    (net (code "91") (name "unconnected-(IC1-PMA11{slash}AN12{slash}RB12-Pad41)") (class "Default")
      (node (ref "IC1") (pin "41") (pinfunction "PMA11/AN12/RB12_41") (pintype "bidirectional"))
    )
    (net (code "92") (name "unconnected-(IC1-PMA12{slash}AN11{slash}RB11-Pad35)") (class "Default")
      (node (ref "IC1") (pin "35") (pinfunction "PMA12/AN11/RB11_35") (pintype "bidirectional"))
    )
    (net (code "93") (name "unconnected-(IC1-PMA13{slash}CVREF{slash}AN10{slash}RB10-Pad34)") (class "Default")
      (node (ref "IC1") (pin "34") (pinfunction "PMA13/CVREF/AN10/RB10_34") (pintype "bidirectional"))
    )
    (net (code "94") (name "unconnected-(IC1-PMBE{slash}OC4{slash}RD3-Pad78)") (class "Default")
      (node (ref "IC1") (pin "78") (pinfunction "PMBE/OC4/RD3_78") (pintype "bidirectional"))
    )
    (net (code "95") (name "unconnected-(IC1-RA6-Pad91)") (class "Default")
      (node (ref "IC1") (pin "91") (pinfunction "RA6_91") (pintype "bidirectional"))
    )
    (net (code "96") (name "unconnected-(IC1-RA7-Pad92)") (class "Default")
      (node (ref "IC1") (pin "92") (pinfunction "RA7_92") (pintype "bidirectional"))
    )
    (net (code "97") (name "unconnected-(IC1-RF0-Pad87)") (class "Default")
      (node (ref "IC1") (pin "87") (pinfunction "RF0_87") (pintype "bidirectional"))
    )
    (net (code "98") (name "unconnected-(IC1-RF1-Pad88)") (class "Default")
      (node (ref "IC1") (pin "88") (pinfunction "RF1_88") (pintype "bidirectional"))
    )
    (net (code "99") (name "unconnected-(IC1-RG0-Pad90)") (class "Default")
      (node (ref "IC1") (pin "90") (pinfunction "RG0_90") (pintype "bidirectional"))
    )
    (net (code "100") (name "unconnected-(IC1-RG1-Pad89)") (class "Default")
      (node (ref "IC1") (pin "89") (pinfunction "RG1_89") (pintype "bidirectional"))
    )
    (net (code "101") (name "unconnected-(IC1-RG12-Pad96)") (class "Default")
      (node (ref "IC1") (pin "96") (pinfunction "RG12_96") (pintype "bidirectional"))
    )
    (net (code "102") (name "unconnected-(IC1-RG13-Pad97)") (class "Default")
      (node (ref "IC1") (pin "97") (pinfunction "RG13_97") (pintype "bidirectional"))
    )
    (net (code "103") (name "unconnected-(IC1-RG14-Pad95)") (class "Default")
      (node (ref "IC1") (pin "95") (pinfunction "RG14_95") (pintype "bidirectional"))
    )
    (net (code "104") (name "unconnected-(IC1-RG15-Pad1)") (class "Default")
      (node (ref "IC1") (pin "1") (pinfunction "RG15_1") (pintype "bidirectional"))
    )
    (net (code "105") (name "unconnected-(IC1-SOSCI{slash}CN1{slash}RC13-Pad73)") (class "Default")
      (node (ref "IC1") (pin "73") (pinfunction "SOSCI/CN1/RC13_73") (pintype "bidirectional"))
    )
    (net (code "106") (name "unconnected-(IC1-SOSCO{slash}T1CK{slash}CN0{slash}RC14-Pad74)") (class "Default")
      (node (ref "IC1") (pin "74") (pinfunction "SOSCO/T1CK/CN0/RC14_74") (pintype "bidirectional"))
    )
    (net (code "107") (name "unconnected-(IC1-T2CK{slash}RC1-Pad6)") (class "Default")
      (node (ref "IC1") (pin "6") (pinfunction "T2CK/RC1_6") (pintype "bidirectional"))
    )
    (net (code "108") (name "unconnected-(IC1-T3CK{slash}RC2-Pad7)") (class "Default")
      (node (ref "IC1") (pin "7") (pinfunction "T3CK/RC2_7") (pintype "bidirectional"))
    )
    (net (code "109") (name "unconnected-(IC1-T4CK{slash}RC3-Pad8)") (class "Default")
      (node (ref "IC1") (pin "8") (pinfunction "T4CK/RC3_8") (pintype "bidirectional"))
    )
    (net (code "110") (name "unconnected-(IC1-T5CK{slash}RC4-Pad9)") (class "Default")
      (node (ref "IC1") (pin "9") (pinfunction "T5CK/RC4_9") (pintype "bidirectional"))
    )
    (net (code "111") (name "unconnected-(IC1-TCK{slash}RA1-Pad38)") (class "Default")
      (node (ref "IC1") (pin "38") (pinfunction "TCK/RA1_38") (pintype "bidirectional"))
    )
    (net (code "112") (name "unconnected-(IC1-TDI{slash}RA4-Pad60)") (class "Default")
      (node (ref "IC1") (pin "60") (pinfunction "TDI/RA4_60") (pintype "bidirectional"))
    )
    (net (code "113") (name "unconnected-(IC1-TDO{slash}RA5-Pad61)") (class "Default")
      (node (ref "IC1") (pin "61") (pinfunction "TDO/RA5_61") (pintype "bidirectional"))
    )
    (net (code "114") (name "unconnected-(IC1-TMS{slash}RA0-Pad17)") (class "Default")
      (node (ref "IC1") (pin "17") (pinfunction "TMS/RA0_17") (pintype "bidirectional"))
    )
    (net (code "115") (name "unconnected-(IC1-U1RX{slash}RF2-Pad52)") (class "Default")
      (node (ref "IC1") (pin "52") (pinfunction "U1RX/RF2_52") (pintype "bidirectional"))
    )
    (net (code "116") (name "unconnected-(IC1-U1TX{slash}RF3-Pad51)") (class "Default")
      (node (ref "IC1") (pin "51") (pinfunction "U1TX/RF3_51") (pintype "bidirectional"))
    )
    (net (code "117") (name "unconnected-(IC1-~{U1CTS{slash}CN20{slash}RD14}-Pad47)") (class "Default")
      (node (ref "IC1") (pin "47") (pinfunction "~{U1CTS/CN20/RD14}_47") (pintype "bidirectional"))
    )
    (net (code "118") (name "unconnected-(IC1-~{U1RTS{slash}BCLK1{slash}CN21{slash}RD15}-Pad48)") (class "Default")
      (node (ref "IC1") (pin "48") (pinfunction "~{U1RTS/BCLK1/CN21/RD15}_48") (pintype "bidirectional"))
    )
    (net (code "119") (name "unconnected-(IC1-~{U2CTS{slash}RF12}-Pad40)") (class "Default")
      (node (ref "IC1") (pin "40") (pinfunction "~{U2CTS/RF12}_40") (pintype "bidirectional"))
    )
    (net (code "120") (name "unconnected-(IC1-~{U2RTS{slash}BCLK2{slash}RF13}-Pad39)") (class "Default")
      (node (ref "IC1") (pin "39") (pinfunction "~{U2RTS/BCLK2/RF13}_39") (pintype "bidirectional"))
    )
    (net (code "121") (name "unconnected-(IC2-OUT-Pad4)") (class "Default")
      (node (ref "IC2") (pin "4") (pinfunction "OUT_4") (pintype "output"))
    )
    (net (code "122") (name "unconnected-(J1-Pad6)") (class "Default")
      (node (ref "J1") (pin "6") (pinfunction "6_6") (pintype "passive"))
    )
    (net (code "123") (name "unconnected-(JP2-Pad5)") (class "Default")
      (node (ref "JP2") (pin "5") (pinfunction "5_5") (pintype "passive"))
    )
    (net (code "124") (name "unconnected-(JP2-Pad6)") (class "Default")
      (node (ref "JP2") (pin "6") (pinfunction "6_6") (pintype "passive"))
    )
    (net (code "125") (name "unconnected-(JP2-Pad8)") (class "Default")
      (node (ref "JP2") (pin "8") (pinfunction "8_8") (pintype "passive"))
    )
    (net (code "126") (name "unconnected-(U$3-1_ONB-Pad1)") (class "Default")
      (node (ref "U$3") (pin "1") (pinfunction "1_ONB_1") (pintype "bidirectional"))
    )
    (net (code "127") (name "unconnected-(U$3-2_ONA-Pad2)") (class "Default")
      (node (ref "U$3") (pin "2") (pinfunction "2_ONA_2") (pintype "bidirectional"))
    )
    (net (code "128") (name "unconnected-(U$7-Pad2)") (class "Default")
      (node (ref "U$7") (pin "2") (pinfunction "2_2") (pintype "input"))
    )
    (net (code "129") (name "unconnected-(U$7-Pad3)") (class "Default")
      (node (ref "U$7") (pin "3") (pinfunction "3_3") (pintype "input"))
    )
    (net (code "130") (name "unconnected-(U$7-Pad4)") (class "Default")
      (node (ref "U$7") (pin "4") (pinfunction "4_4") (pintype "input"))
    )
  )
)
